# Relay_Drivers.net
KiCad netlist of a schematic drawn in Altium Designer
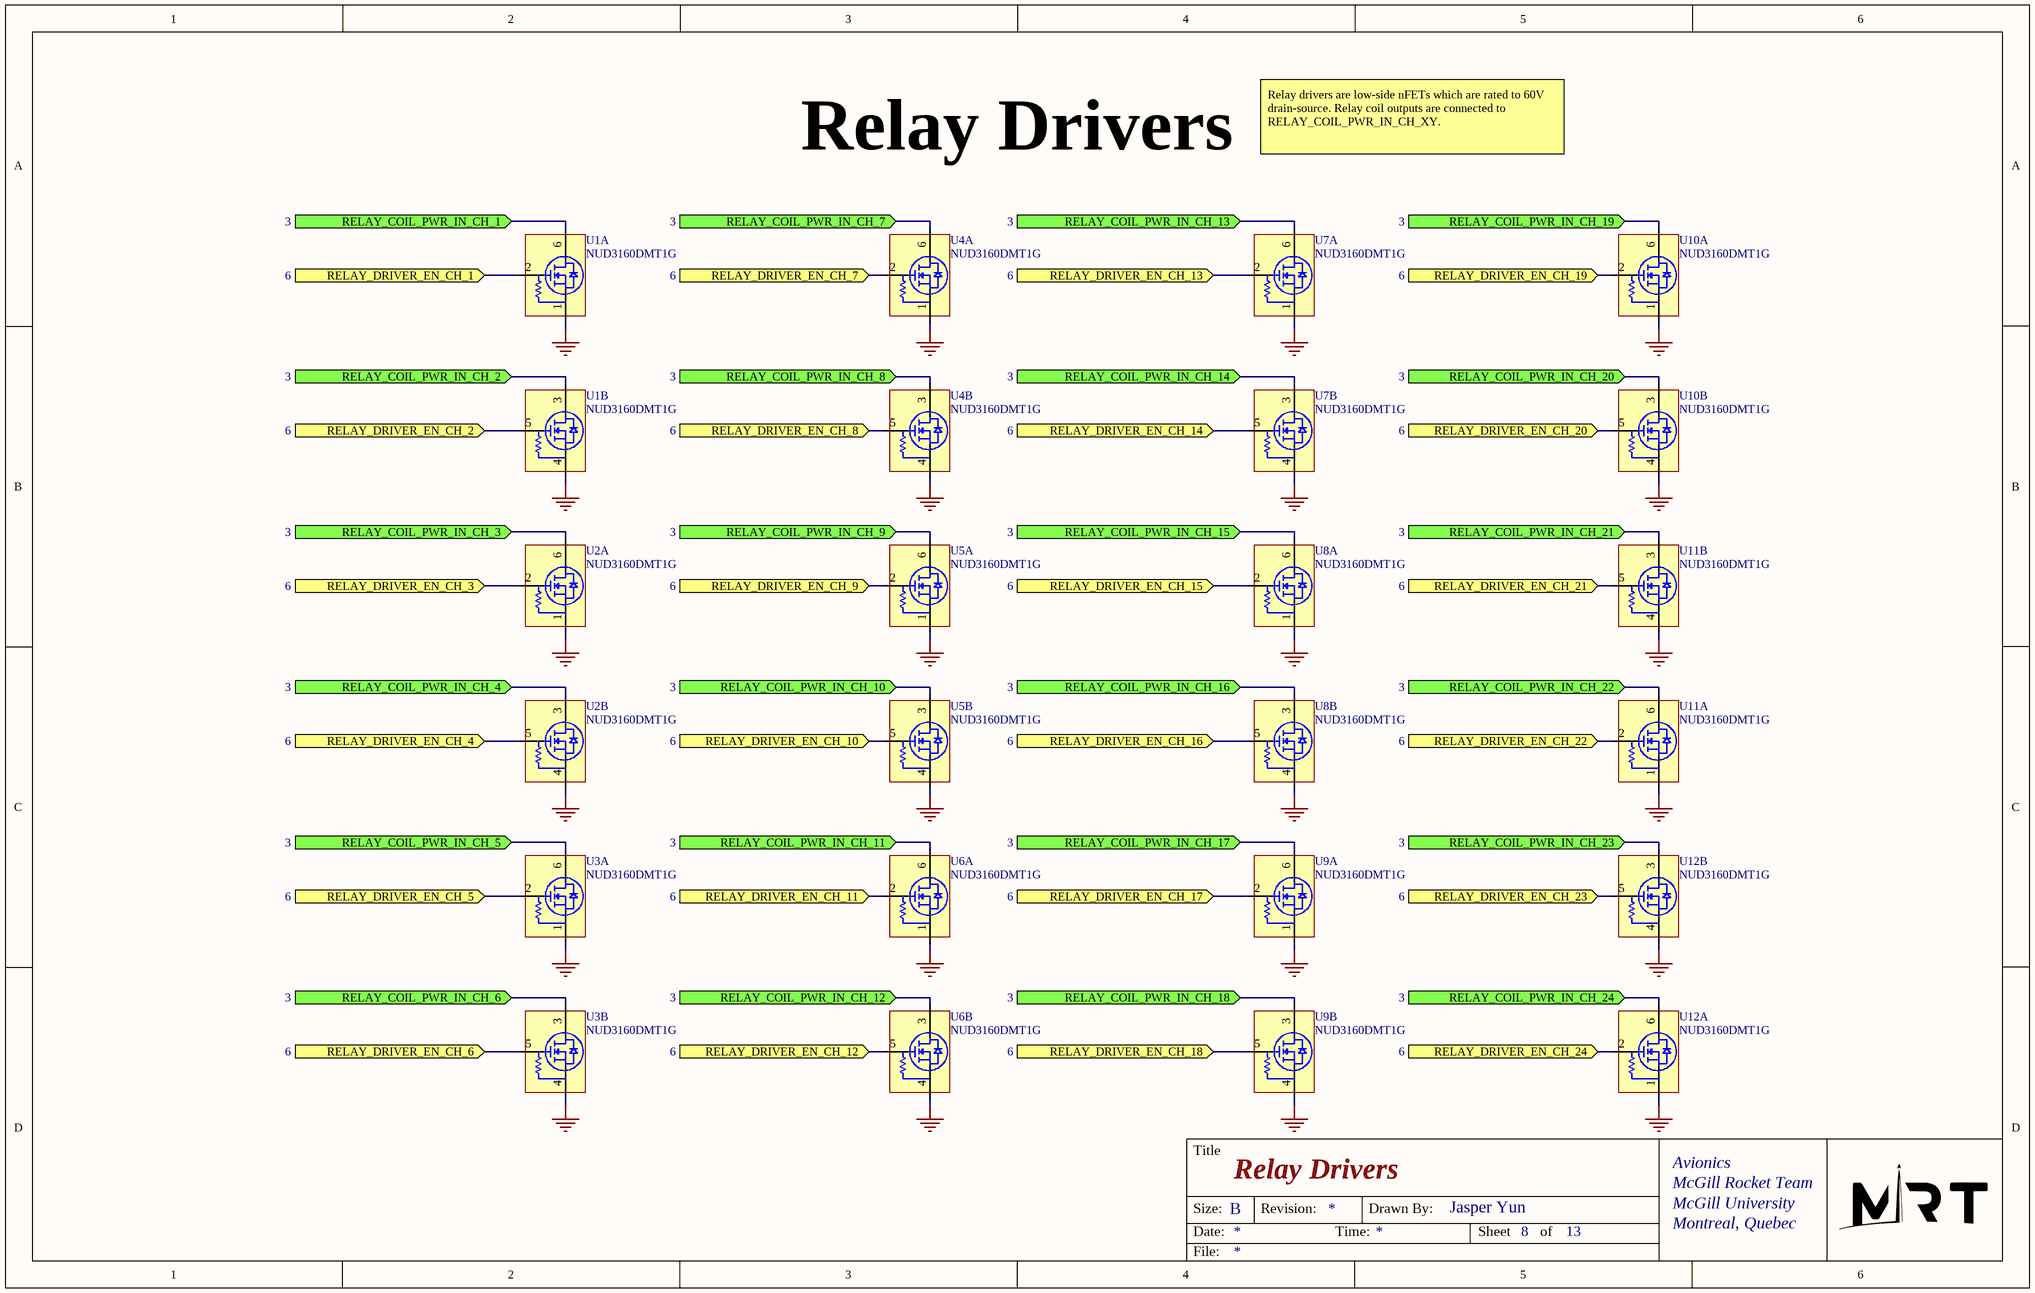
[diagram p0: Relay Drivers.SchDoc]

(export (version "E")
  (design (tool "Eeschema 10.0.6"))
  (components
    (comp (ref "U1")
      (value "NUD3160DMT1G")
      (footprint "SOT23-6")
      (description "IC INDCT LOAD DRVR INDUST SC74-6")
      (fields (field (name "MANUFACTURER") "ON Semiconductor"))
      (libsource (lib "MRT SCH Library") (part "Relay Driver Dual NUD3160DMT1G"))
    )
    (comp (ref "U2")
      (value "NUD3160DMT1G")
      (footprint "SOT23-6")
      (description "IC INDCT LOAD DRVR INDUST SC74-6")
      (fields (field (name "MANUFACTURER") "ON Semiconductor"))
      (libsource (lib "MRT SCH Library") (part "Relay Driver Dual NUD3160DMT1G"))
    )
    (comp (ref "U3")
      (value "NUD3160DMT1G")
      (footprint "SOT23-6")
      (description "IC INDCT LOAD DRVR INDUST SC74-6")
      (fields (field (name "MANUFACTURER") "ON Semiconductor"))
      (libsource (lib "MRT SCH Library") (part "Relay Driver Dual NUD3160DMT1G"))
    )
    (comp (ref "U4")
      (value "NUD3160DMT1G")
      (footprint "SOT23-6")
      (description "IC INDCT LOAD DRVR INDUST SC74-6")
      (fields (field (name "MANUFACTURER") "ON Semiconductor"))
      (libsource (lib "MRT SCH Library") (part "Relay Driver Dual NUD3160DMT1G"))
    )
    (comp (ref "U5")
      (value "NUD3160DMT1G")
      (footprint "SOT23-6")
      (description "IC INDCT LOAD DRVR INDUST SC74-6")
      (fields (field (name "MANUFACTURER") "ON Semiconductor"))
      (libsource (lib "MRT SCH Library") (part "Relay Driver Dual NUD3160DMT1G"))
    )
    (comp (ref "U6")
      (value "NUD3160DMT1G")
      (footprint "SOT23-6")
      (description "IC INDCT LOAD DRVR INDUST SC74-6")
      (fields (field (name "MANUFACTURER") "ON Semiconductor"))
      (libsource (lib "MRT SCH Library") (part "Relay Driver Dual NUD3160DMT1G"))
    )
    (comp (ref "U7")
      (value "NUD3160DMT1G")
      (footprint "SOT23-6")
      (description "IC INDCT LOAD DRVR INDUST SC74-6")
      (fields (field (name "MANUFACTURER") "ON Semiconductor"))
      (libsource (lib "MRT SCH Library") (part "Relay Driver Dual NUD3160DMT1G"))
    )
    (comp (ref "U8")
      (value "NUD3160DMT1G")
      (footprint "SOT23-6")
      (description "IC INDCT LOAD DRVR INDUST SC74-6")
      (fields (field (name "MANUFACTURER") "ON Semiconductor"))
      (libsource (lib "MRT SCH Library") (part "Relay Driver Dual NUD3160DMT1G"))
    )
    (comp (ref "U9")
      (value "NUD3160DMT1G")
      (footprint "SOT23-6")
      (description "IC INDCT LOAD DRVR INDUST SC74-6")
      (fields (field (name "MANUFACTURER") "ON Semiconductor"))
      (libsource (lib "MRT SCH Library") (part "Relay Driver Dual NUD3160DMT1G"))
    )
    (comp (ref "U10")
      (value "NUD3160DMT1G")
      (footprint "SOT23-6")
      (description "IC INDCT LOAD DRVR INDUST SC74-6")
      (fields (field (name "MANUFACTURER") "ON Semiconductor"))
      (libsource (lib "MRT SCH Library") (part "Relay Driver Dual NUD3160DMT1G"))
    )
    (comp (ref "U11")
      (value "NUD3160DMT1G")
      (footprint "SOT23-6")
      (description "IC INDCT LOAD DRVR INDUST SC74-6")
      (fields (field (name "MANUFACTURER") "ON Semiconductor"))
      (libsource (lib "MRT SCH Library") (part "Relay Driver Dual NUD3160DMT1G"))
    )
    (comp (ref "U12")
      (value "NUD3160DMT1G")
      (footprint "SOT23-6")
      (description "IC INDCT LOAD DRVR INDUST SC74-6")
      (fields (field (name "MANUFACTURER") "ON Semiconductor"))
      (libsource (lib "MRT SCH Library") (part "Relay Driver Dual NUD3160DMT1G"))
    )
  )
  (nets
    (net (code "1") (name "/RELAY_COIL_PWR_IN_CH_1") (class "Default")
      (node (ref "U1") (pin "6") (pinfunction "Drain_6") (pintype "passive"))
    )
    (net (code "2") (name "/RELAY_COIL_PWR_IN_CH_2") (class "Default")
      (node (ref "U1") (pin "3") (pinfunction "Drain_3") (pintype "passive"))
    )
    (net (code "3") (name "/RELAY_COIL_PWR_IN_CH_3") (class "Default")
      (node (ref "U2") (pin "6") (pinfunction "Drain_6") (pintype "passive"))
    )
    (net (code "4") (name "/RELAY_COIL_PWR_IN_CH_4") (class "Default")
      (node (ref "U2") (pin "3") (pinfunction "Drain_3") (pintype "passive"))
    )
    (net (code "5") (name "/RELAY_COIL_PWR_IN_CH_5") (class "Default")
      (node (ref "U3") (pin "6") (pinfunction "Drain_6") (pintype "passive"))
    )
    (net (code "6") (name "/RELAY_COIL_PWR_IN_CH_6") (class "Default")
      (node (ref "U3") (pin "3") (pinfunction "Drain_3") (pintype "passive"))
    )
    (net (code "7") (name "/RELAY_COIL_PWR_IN_CH_7") (class "Default")
      (node (ref "U4") (pin "6") (pinfunction "Drain_6") (pintype "passive"))
    )
    (net (code "8") (name "/RELAY_COIL_PWR_IN_CH_8") (class "Default")
      (node (ref "U4") (pin "3") (pinfunction "Drain_3") (pintype "passive"))
    )
    (net (code "9") (name "/RELAY_COIL_PWR_IN_CH_9") (class "Default")
      (node (ref "U5") (pin "6") (pinfunction "Drain_6") (pintype "passive"))
    )
    (net (code "10") (name "/RELAY_COIL_PWR_IN_CH_10") (class "Default")
      (node (ref "U5") (pin "3") (pinfunction "Drain_3") (pintype "passive"))
    )
    (net (code "11") (name "/RELAY_COIL_PWR_IN_CH_11") (class "Default")
      (node (ref "U6") (pin "6") (pinfunction "Drain_6") (pintype "passive"))
    )
    (net (code "12") (name "/RELAY_COIL_PWR_IN_CH_12") (class "Default")
      (node (ref "U6") (pin "3") (pinfunction "Drain_3") (pintype "passive"))
    )
    (net (code "13") (name "/RELAY_COIL_PWR_IN_CH_13") (class "Default")
      (node (ref "U7") (pin "6") (pinfunction "Drain_6") (pintype "passive"))
    )
    (net (code "14") (name "/RELAY_COIL_PWR_IN_CH_14") (class "Default")
      (node (ref "U7") (pin "3") (pinfunction "Drain_3") (pintype "passive"))
    )
    (net (code "15") (name "/RELAY_COIL_PWR_IN_CH_15") (class "Default")
      (node (ref "U8") (pin "6") (pinfunction "Drain_6") (pintype "passive"))
    )
    (net (code "16") (name "/RELAY_COIL_PWR_IN_CH_16") (class "Default")
      (node (ref "U8") (pin "3") (pinfunction "Drain_3") (pintype "passive"))
    )
    (net (code "17") (name "/RELAY_COIL_PWR_IN_CH_17") (class "Default")
      (node (ref "U9") (pin "6") (pinfunction "Drain_6") (pintype "passive"))
    )
    (net (code "18") (name "/RELAY_COIL_PWR_IN_CH_18") (class "Default")
      (node (ref "U9") (pin "3") (pinfunction "Drain_3") (pintype "passive"))
    )
    (net (code "19") (name "/RELAY_COIL_PWR_IN_CH_19") (class "Default")
      (node (ref "U10") (pin "6") (pinfunction "Drain_6") (pintype "passive"))
    )
    (net (code "20") (name "/RELAY_COIL_PWR_IN_CH_20") (class "Default")
      (node (ref "U10") (pin "3") (pinfunction "Drain_3") (pintype "passive"))
    )
    (net (code "21") (name "/RELAY_COIL_PWR_IN_CH_21") (class "Default")
      (node (ref "U11") (pin "3") (pinfunction "Drain_3") (pintype "passive"))
    )
    (net (code "22") (name "/RELAY_COIL_PWR_IN_CH_22") (class "Default")
      (node (ref "U11") (pin "6") (pinfunction "Drain_6") (pintype "passive"))
    )
    (net (code "23") (name "/RELAY_COIL_PWR_IN_CH_23") (class "Default")
      (node (ref "U12") (pin "3") (pinfunction "Drain_3") (pintype "passive"))
    )
    (net (code "24") (name "/RELAY_COIL_PWR_IN_CH_24") (class "Default")
      (node (ref "U12") (pin "6") (pinfunction "Drain_6") (pintype "passive"))
    )
    (net (code "25") (name "/RELAY_DRIVER_EN_CH_1") (class "Default")
      (node (ref "U1") (pin "2") (pinfunction "Gate_2") (pintype "passive"))
    )
    (net (code "26") (name "/RELAY_DRIVER_EN_CH_2") (class "Default")
      (node (ref "U1") (pin "5") (pinfunction "Gate_5") (pintype "passive"))
    )
    (net (code "27") (name "/RELAY_DRIVER_EN_CH_3") (class "Default")
      (node (ref "U2") (pin "2") (pinfunction "Gate_2") (pintype "passive"))
    )
    (net (code "28") (name "/RELAY_DRIVER_EN_CH_4") (class "Default")
      (node (ref "U2") (pin "5") (pinfunction "Gate_5") (pintype "passive"))
    )
    (net (code "29") (name "/RELAY_DRIVER_EN_CH_5") (class "Default")
      (node (ref "U3") (pin "2") (pinfunction "Gate_2") (pintype "passive"))
    )
    (net (code "30") (name "/RELAY_DRIVER_EN_CH_6") (class "Default")
      (node (ref "U3") (pin "5") (pinfunction "Gate_5") (pintype "passive"))
    )
    (net (code "31") (name "/RELAY_DRIVER_EN_CH_7") (class "Default")
      (node (ref "U4") (pin "2") (pinfunction "Gate_2") (pintype "passive"))
    )
    (net (code "32") (name "/RELAY_DRIVER_EN_CH_8") (class "Default")
      (node (ref "U4") (pin "5") (pinfunction "Gate_5") (pintype "passive"))
    )
    (net (code "33") (name "/RELAY_DRIVER_EN_CH_9") (class "Default")
      (node (ref "U5") (pin "2") (pinfunction "Gate_2") (pintype "passive"))
    )
    (net (code "34") (name "/RELAY_DRIVER_EN_CH_10") (class "Default")
      (node (ref "U5") (pin "5") (pinfunction "Gate_5") (pintype "passive"))
    )
    (net (code "35") (name "/RELAY_DRIVER_EN_CH_11") (class "Default")
      (node (ref "U6") (pin "2") (pinfunction "Gate_2") (pintype "passive"))
    )
    (net (code "36") (name "/RELAY_DRIVER_EN_CH_12") (class "Default")
      (node (ref "U6") (pin "5") (pinfunction "Gate_5") (pintype "passive"))
    )
    (net (code "37") (name "/RELAY_DRIVER_EN_CH_13") (class "Default")
      (node (ref "U7") (pin "2") (pinfunction "Gate_2") (pintype "passive"))
    )
    (net (code "38") (name "/RELAY_DRIVER_EN_CH_14") (class "Default")
      (node (ref "U7") (pin "5") (pinfunction "Gate_5") (pintype "passive"))
    )
    (net (code "39") (name "/RELAY_DRIVER_EN_CH_15") (class "Default")
      (node (ref "U8") (pin "2") (pinfunction "Gate_2") (pintype "passive"))
    )
    (net (code "40") (name "/RELAY_DRIVER_EN_CH_16") (class "Default")
      (node (ref "U8") (pin "5") (pinfunction "Gate_5") (pintype "passive"))
    )
    (net (code "41") (name "/RELAY_DRIVER_EN_CH_17") (class "Default")
      (node (ref "U9") (pin "2") (pinfunction "Gate_2") (pintype "passive"))
    )
    (net (code "42") (name "/RELAY_DRIVER_EN_CH_18") (class "Default")
      (node (ref "U9") (pin "5") (pinfunction "Gate_5") (pintype "passive"))
    )
    (net (code "43") (name "/RELAY_DRIVER_EN_CH_19") (class "Default")
      (node (ref "U10") (pin "2") (pinfunction "Gate_2") (pintype "passive"))
    )
    (net (code "44") (name "/RELAY_DRIVER_EN_CH_20") (class "Default")
      (node (ref "U10") (pin "5") (pinfunction "Gate_5") (pintype "passive"))
    )
    (net (code "45") (name "/RELAY_DRIVER_EN_CH_21") (class "Default")
      (node (ref "U11") (pin "5") (pinfunction "Gate_5") (pintype "passive"))
    )
    (net (code "46") (name "/RELAY_DRIVER_EN_CH_22") (class "Default")
      (node (ref "U11") (pin "2") (pinfunction "Gate_2") (pintype "passive"))
    )
    (net (code "47") (name "/RELAY_DRIVER_EN_CH_23") (class "Default")
      (node (ref "U12") (pin "5") (pinfunction "Gate_5") (pintype "passive"))
    )
    (net (code "48") (name "/RELAY_DRIVER_EN_CH_24") (class "Default")
      (node (ref "U12") (pin "2") (pinfunction "Gate_2") (pintype "passive"))
    )
    (net (code "49") (name "GND") (class "Default")
      (node (ref "U1") (pin "1") (pinfunction "Source_1") (pintype "passive"))
      (node (ref "U1") (pin "4") (pinfunction "Source_4") (pintype "passive"))
      (node (ref "U10") (pin "1") (pinfunction "Source_1") (pintype "passive"))
      (node (ref "U10") (pin "4") (pinfunction "Source_4") (pintype "passive"))
      (node (ref "U11") (pin "1") (pinfunction "Source_1") (pintype "passive"))
      (node (ref "U11") (pin "4") (pinfunction "Source_4") (pintype "passive"))
      (node (ref "U12") (pin "1") (pinfunction "Source_1") (pintype "passive"))
      (node (ref "U12") (pin "4") (pinfunction "Source_4") (pintype "passive"))
      (node (ref "U2") (pin "1") (pinfunction "Source_1") (pintype "passive"))
      (node (ref "U2") (pin "4") (pinfunction "Source_4") (pintype "passive"))
      (node (ref "U3") (pin "1") (pinfunction "Source_1") (pintype "passive"))
      (node (ref "U3") (pin "4") (pinfunction "Source_4") (pintype "passive"))
      (node (ref "U4") (pin "1") (pinfunction "Source_1") (pintype "passive"))
      (node (ref "U4") (pin "4") (pinfunction "Source_4") (pintype "passive"))
      (node (ref "U5") (pin "1") (pinfunction "Source_1") (pintype "passive"))
      (node (ref "U5") (pin "4") (pinfunction "Source_4") (pintype "passive"))
      (node (ref "U6") (pin "1") (pinfunction "Source_1") (pintype "passive"))
      (node (ref "U6") (pin "4") (pinfunction "Source_4") (pintype "passive"))
      (node (ref "U7") (pin "1") (pinfunction "Source_1") (pintype "passive"))
      (node (ref "U7") (pin "4") (pinfunction "Source_4") (pintype "passive"))
      (node (ref "U8") (pin "1") (pinfunction "Source_1") (pintype "passive"))
      (node (ref "U8") (pin "4") (pinfunction "Source_4") (pintype "passive"))
      (node (ref "U9") (pin "1") (pinfunction "Source_1") (pintype "passive"))
      (node (ref "U9") (pin "4") (pinfunction "Source_4") (pintype "passive"))
    )
  )
)
